# Sensor_Board.net
KiCad netlist of a schematic drawn in Altium Designer
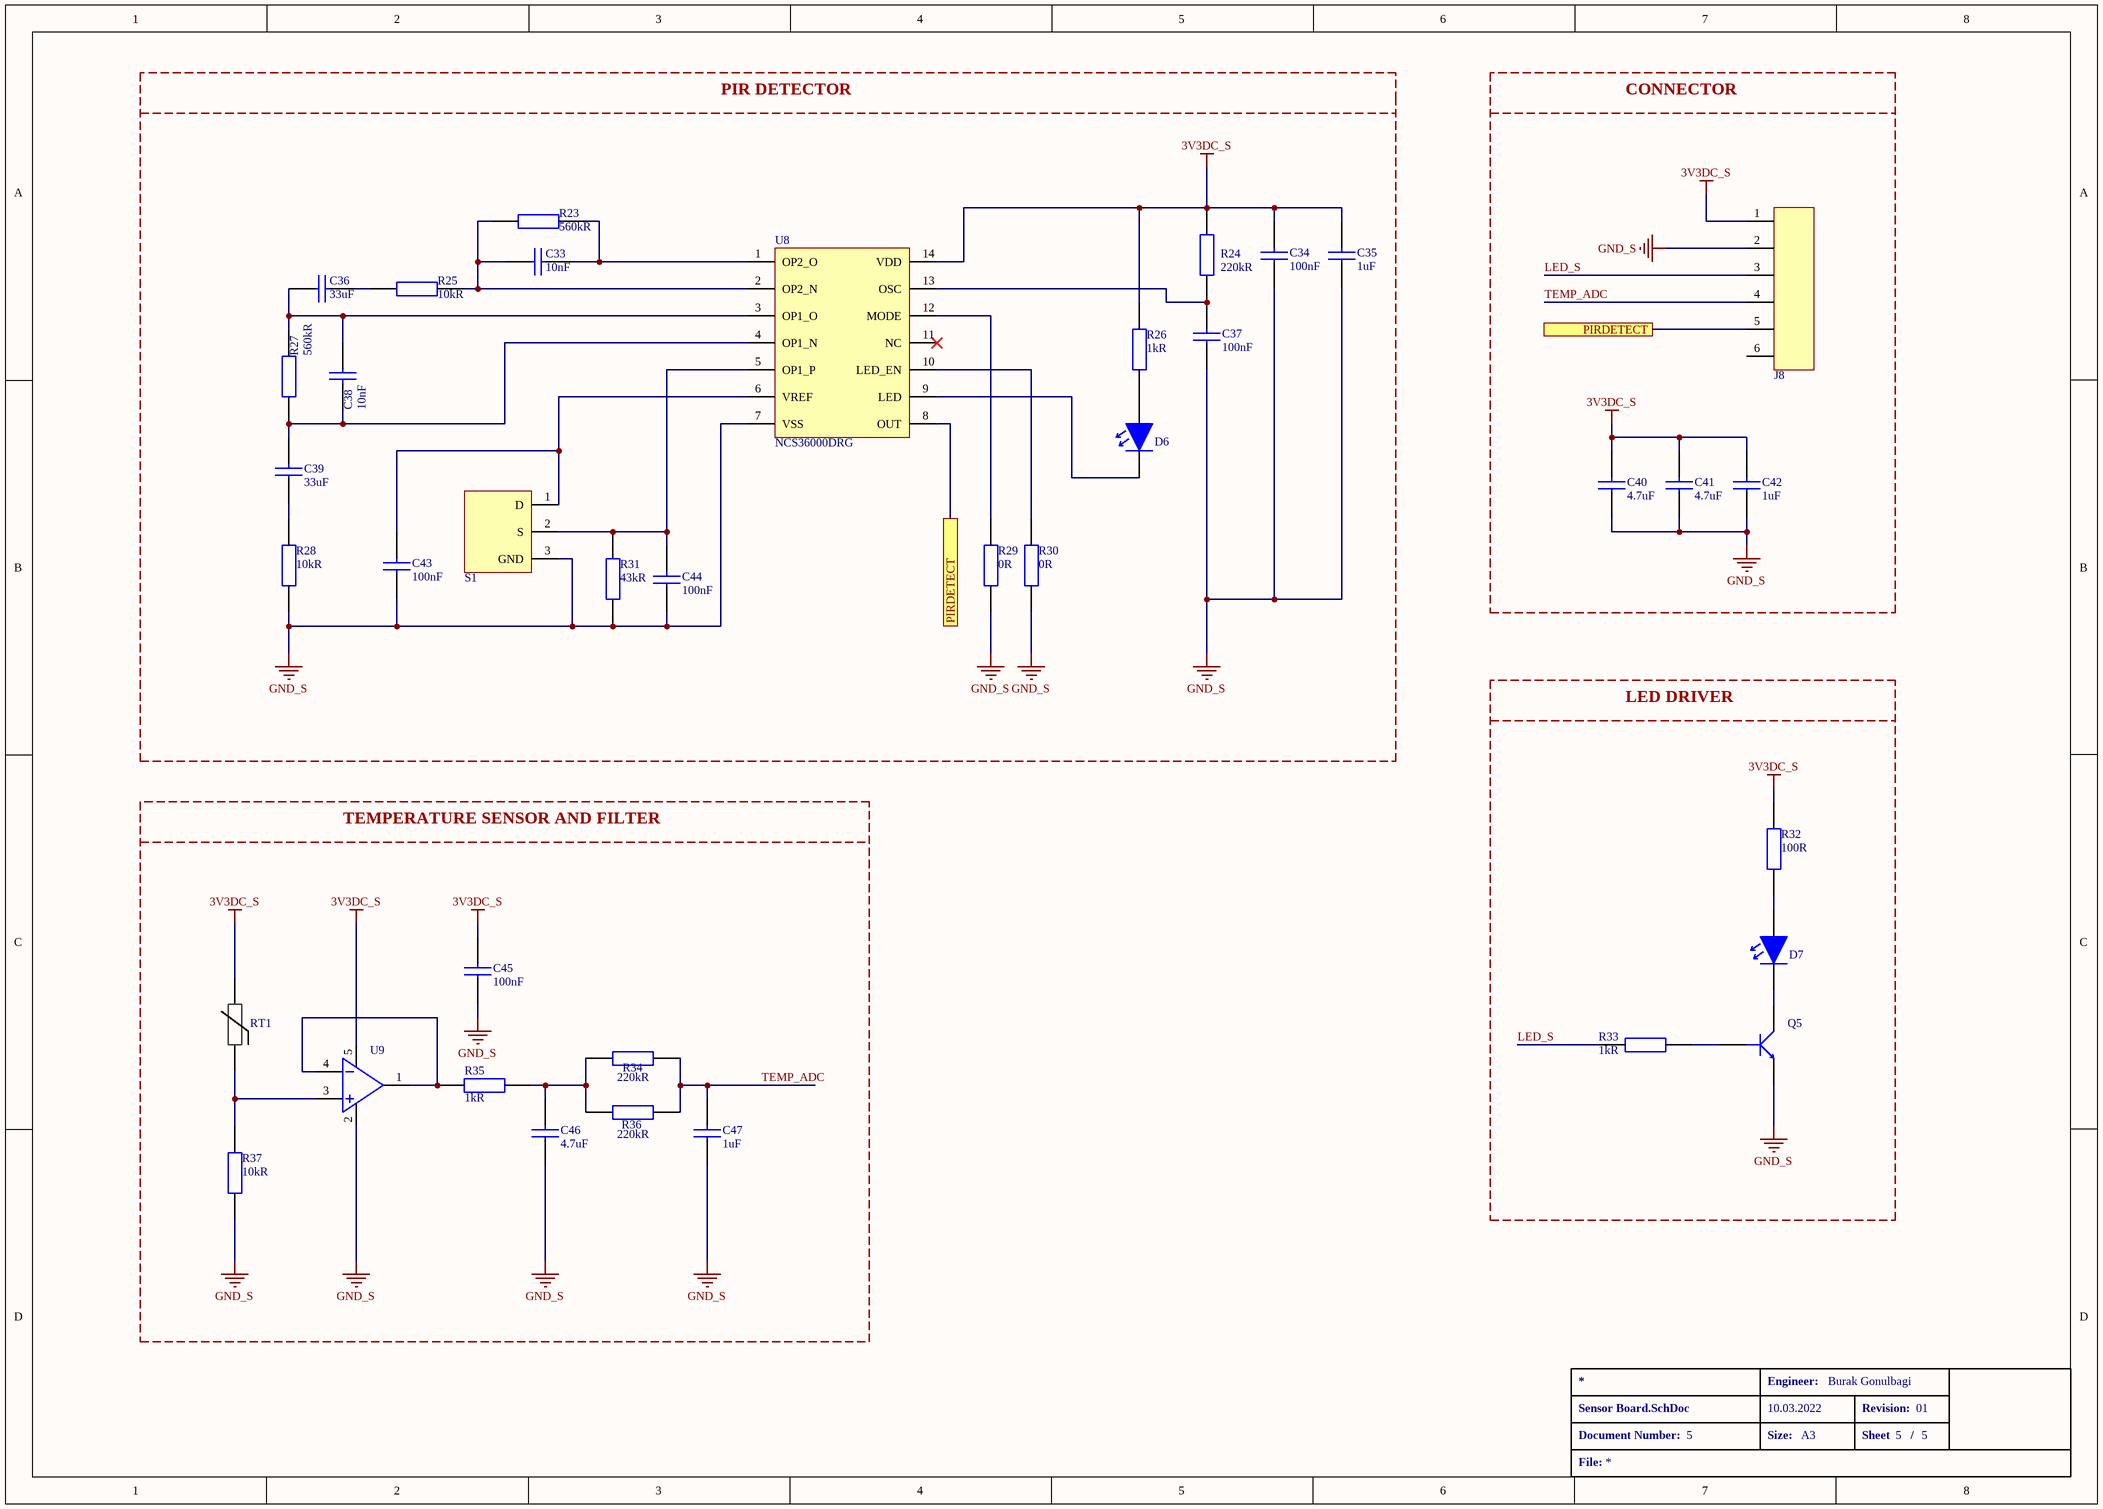
[diagram p0: Sensor Board.SchDoc]

(export (version "E")
  (design (tool "Eeschema 10.0.6"))
  (components
    (comp (ref "C33")
      (value "0603B103K160CT")
      (footprint "CAP_0603")
      (description "CAP CER 10nF %10 0603")
      (fields
        (field (name "MANUFACTURER") "Walsin Technologies")
        (field (name "TOLERANCE") "10%")
        (field (name "CAPACITANCE") "10nF")
        (field (name "DESIGNED BY") "BERK")
      )
      (libsource (lib "UDEMY_Library") (part "CAP CER 10nF 0603"))
    )
    (comp (ref "C34")
      (value "C0603C104K5RACTU")
      (footprint "CAP_0603")
      (description "CAP CER 100nF %10 0603 SMD")
      (fields
        (field (name "MANUFACTURER") "KEMET")
        (field (name "TOLERANCE") "10%")
        (field (name "CAPACITANCE") "100nF")
        (field (name "DESIGNED BY") "BERK")
      )
      (libsource (lib "UDEMY_Library") (part "CAP CER 100nF 0603"))
    )
    (comp (ref "C35")
      (value "CL21B105KBFNNNE")
      (footprint "CAP_0805")
      (description "CAP CER 1uF %10 0805")
      (fields
        (field (name "MANUFACTURER") "Samsung")
        (field (name "TOLERANCE") "10%")
        (field (name "CAPACITANCE") "1uF")
        (field (name "DESIGNED BY") "BERK")
      )
      (libsource (lib "UDEMY_Library") (part "CAP CER 1uF 0805"))
    )
    (comp (ref "C36")
      (value "C3216X5R1E336M160AC")
      (footprint "CAP_1206")
      (description "CAP CER 33uF %20 1206 SMD")
      (fields
        (field (name "MANUFACTURER") "TDK")
        (field (name "TOLERANCE") "20%")
        (field (name "CAPACITANCE") "33uF")
        (field (name "DESIGNED BY") "BERK")
      )
      (libsource (lib "UDEMY_Library") (part "CAP CER 33uF 1206"))
    )
    (comp (ref "C37")
      (value "C0603C104K5RACTU")
      (footprint "CAP_0603")
      (description "CAP CER 100nF %10 0603 SMD")
      (fields
        (field (name "MANUFACTURER") "KEMET")
        (field (name "TOLERANCE") "10%")
        (field (name "CAPACITANCE") "100nF")
        (field (name "DESIGNED BY") "BERK")
      )
      (libsource (lib "UDEMY_Library") (part "CAP CER 100nF 0603"))
    )
    (comp (ref "C38")
      (value "0603B103K160CT")
      (footprint "CAP_0603")
      (description "CAP CER 10nF %10 0603")
      (fields
        (field (name "MANUFACTURER") "Walsin Technologies")
        (field (name "TOLERANCE") "10%")
        (field (name "CAPACITANCE") "10nF")
        (field (name "DESIGNED BY") "BERK")
      )
      (libsource (lib "UDEMY_Library") (part "CAP CER 10nF 0603"))
    )
    (comp (ref "C39")
      (value "C3216X5R1E336M160AC")
      (footprint "CAP_1206")
      (description "CAP CER 33uF %20 1206 SMD")
      (fields
        (field (name "MANUFACTURER") "TDK")
        (field (name "TOLERANCE") "20%")
        (field (name "CAPACITANCE") "33uF")
        (field (name "DESIGNED BY") "BERK")
      )
      (libsource (lib "UDEMY_Library") (part "CAP CER 33uF 1206"))
    )
    (comp (ref "C40")
      (value "CL21A475KAQNNNE")
      (footprint "CAP_0805")
      (description "CAP CER 4.7uF %10 0805")
      (fields
        (field (name "MANUFACTURER") "Samsung")
        (field (name "TOLERANCE") "10%")
        (field (name "CAPACITANCE") "4.7uF")
        (field (name "DESIGNED BY") "BERK")
      )
      (libsource (lib "UDEMY_Library") (part "CAP CER 4.7uF 0805"))
    )
    (comp (ref "C41")
      (value "CL21A475KAQNNNE")
      (footprint "CAP_0805")
      (description "CAP CER 4.7uF %10 0805")
      (fields
        (field (name "MANUFACTURER") "Samsung")
        (field (name "TOLERANCE") "10%")
        (field (name "CAPACITANCE") "4.7uF")
        (field (name "DESIGNED BY") "BERK")
      )
      (libsource (lib "UDEMY_Library") (part "CAP CER 4.7uF 0805"))
    )
    (comp (ref "C42")
      (value "CL21B105KBFNNNE")
      (footprint "CAP_0805")
      (description "CAP CER 1uF %10 0805")
      (fields
        (field (name "MANUFACTURER") "Samsung")
        (field (name "TOLERANCE") "10%")
        (field (name "CAPACITANCE") "1uF")
        (field (name "DESIGNED BY") "BERK")
      )
      (libsource (lib "UDEMY_Library") (part "CAP CER 1uF 0805"))
    )
    (comp (ref "C43")
      (value "C0603C104K5RACTU")
      (footprint "CAP_0603")
      (description "CAP CER 100nF %10 0603 SMD")
      (fields
        (field (name "MANUFACTURER") "KEMET")
        (field (name "TOLERANCE") "10%")
        (field (name "CAPACITANCE") "100nF")
        (field (name "DESIGNED BY") "BERK")
      )
      (libsource (lib "UDEMY_Library") (part "CAP CER 100nF 0603"))
    )
    (comp (ref "C44")
      (value "C0603C104K5RACTU")
      (footprint "CAP_0603")
      (description "CAP CER 100nF %10 0603 SMD")
      (fields
        (field (name "MANUFACTURER") "KEMET")
        (field (name "TOLERANCE") "10%")
        (field (name "CAPACITANCE") "100nF")
        (field (name "DESIGNED BY") "BERK")
      )
      (libsource (lib "UDEMY_Library") (part "CAP CER 100nF 0603"))
    )
    (comp (ref "C45")
      (value "C0603C104K5RACTU")
      (footprint "CAP_0603")
      (description "CAP CER 100nF %10 0603 SMD")
      (fields
        (field (name "MANUFACTURER") "KEMET")
        (field (name "TOLERANCE") "10%")
        (field (name "CAPACITANCE") "100nF")
        (field (name "DESIGNED BY") "BERK")
      )
      (libsource (lib "UDEMY_Library") (part "CAP CER 100nF 0603"))
    )
    (comp (ref "C46")
      (value "CL21A475KAQNNNE")
      (footprint "CAP_0805")
      (description "CAP CER 4.7uF %10 0805")
      (fields
        (field (name "MANUFACTURER") "Samsung")
        (field (name "TOLERANCE") "10%")
        (field (name "CAPACITANCE") "4.7uF")
        (field (name "DESIGNED BY") "BERK")
      )
      (libsource (lib "UDEMY_Library") (part "CAP CER 4.7uF 0805"))
    )
    (comp (ref "C47")
      (value "CL21B105KBFNNNE")
      (footprint "CAP_0805")
      (description "CAP CER 1uF %10 0805")
      (fields
        (field (name "MANUFACTURER") "Samsung")
        (field (name "TOLERANCE") "10%")
        (field (name "CAPACITANCE") "1uF")
        (field (name "DESIGNED BY") "BERK")
      )
      (libsource (lib "UDEMY_Library") (part "CAP CER 1uF 0805"))
    )
    (comp (ref "D6")
      (value "LTST-C171GKT")
      (footprint "LED_GREEN_0805")
      (description "Green 0805 130 º Min 5 mcd Typical 12 mcd Water Clear Lens SMT LED")
      (fields (field (name "MANUFACTURER") "Vishay Lite-On") (field (name "DESIGNED BY") "BERK"))
      (libsource (lib "UDEMY_Library") (part "LED GREEN 0805"))
    )
    (comp (ref "D7")
      (value "LH R974-LP-1")
      (footprint "LED_RED_0805")
      (description "LED Uni-Color Hyper Red 660nm 2-Pin Chip 0805(2012Metric) T/R")
      (fields (field (name "MANUFACTURER") "Osram Opto") (field (name "DESIGNED BY") "BERK"))
      (libsource (lib "UDEMY_Library") (part "LED RED 0805"))
    )
    (comp (ref "J8")
      (value "64800611622")
      (footprint "64800611622")
      (description "1.50mm 6PIN Connector")
      (fields (field (name "MANUFACTURER") "Wurth Electronics"))
      (libsource (lib "UDEMY_Library") (part "64800611622_conn_6pin"))
    )
    (comp (ref "Q5")
      (value "MMBT3904-7-F")
      (footprint "SOT-23F")
      (description "Transistor General Purpose BJT NPN 40 Volt 0.2A Automotive 3-Pin SOT-23")
      (fields (field (name "MANUFACTURER") "Diodes Zetex") (field (name "DESIGNED BY") "BERK"))
      (libsource (lib "UDEMY_Library") (part "MMBT3904-7-F"))
    )
    (comp (ref "R23")
      (value "RC0603JR-07560KL")
      (footprint "RES_0603")
      (description "RES SMD 560K OHM 5% 1/10W 0603")
      (fields
        (field (name "MANUFACTURER") "Yageo")
        (field (name "TOLERANCE") "5%")
        (field (name "RESISTANCE") "560kR")
        (field (name "DESIGNED BY") "BERK")
      )
      (libsource (lib "") (part "RES 560K OHM 0603_1"))
    )
    (comp (ref "R24")
      (value "RC0603JR-07220KL")
      (footprint "RES_0603")
      (description "RES 220K %5 OHM 0603 SMD")
      (fields
        (field (name "MANUFACTURER") "Yageo")
        (field (name "TOLERANCE") "5%")
        (field (name "RESISTANCE") "220kR")
      )
      (libsource (lib "") (part "RES 220K OHM 0603_1"))
    )
    (comp (ref "R25")
      (value "RC0603FR-0710KL")
      (footprint "RES_0603")
      (description "RES 10K %1 OHM 0603 SMD")
      (fields
        (field (name "MANUFACTURER") "Yageo")
        (field (name "TOLERANCE") "1%")
        (field (name "RESISTANCE") "10kR")
        (field (name "DESIGNED BY") "BERK")
      )
      (libsource (lib "") (part "RES 10K OHM 0603_1"))
    )
    (comp (ref "R26")
      (value "RC0603FR-0710KL")
      (footprint "RES_0603")
      (description "RES 1K %1 OHM 0603 SMD")
      (fields
        (field (name "MANUFACTURER") "Yageo")
        (field (name "MANUFACTURER PART NUMBER") "RC0603JR-071KL")
        (field (name "RESISTANCE") "1kR")
        (field (name "DESIGNED BY") "BERK")
      )
      (libsource (lib "UDEMY_Library") (part "RES 1K OHM 0603"))
    )
    (comp (ref "R27")
      (value "RC0603JR-07560KL")
      (footprint "RES_0603")
      (description "RES SMD 560K OHM 5% 1/10W 0603")
      (fields
        (field (name "MANUFACTURER") "Yageo")
        (field (name "TOLERANCE") "5%")
        (field (name "RESISTANCE") "560kR")
        (field (name "DESIGNED BY") "BERK")
      )
      (libsource (lib "UDEMY_Library") (part "RES 560K OHM 0603"))
    )
    (comp (ref "R28")
      (value "RC0603FR-0710KL")
      (footprint "RES_0603")
      (description "RES 10K %1 OHM 0603 SMD")
      (fields
        (field (name "MANUFACTURER") "Yageo")
        (field (name "TOLERANCE") "1%")
        (field (name "RESISTANCE") "10kR")
        (field (name "DESIGNED BY") "BERK")
      )
      (libsource (lib "UDEMY_Library") (part "RES 10K OHM 0603"))
    )
    (comp (ref "R29")
      (value "RC0603JR-070RL")
      (footprint "RES_0603")
      (description "RES 0 %1 OHM 0603 SMD")
      (fields
        (field (name "MANUFACTURER") "Yageo")
        (field (name "TOLERANCE") "1%")
        (field (name "RESISTANCE") "0R")
        (field (name "DESIGNED BY") "BERK")
      )
      (libsource (lib "UDEMY_Library") (part "RES 0 OHM 0603"))
    )
    (comp (ref "R30")
      (value "RC0603JR-070RL")
      (footprint "RES_0603")
      (description "RES 0 %1 OHM 0603 SMD")
      (fields
        (field (name "MANUFACTURER") "Yageo")
        (field (name "TOLERANCE") "1%")
        (field (name "RESISTANCE") "0R")
        (field (name "DESIGNED BY") "BERK")
      )
      (libsource (lib "UDEMY_Library") (part "RES 0 OHM 0603"))
    )
    (comp (ref "R31")
      (value "RC0603JR-0743KL")
      (footprint "RES_0603")
      (description "RES 43K %5 OHM 0603 SMD")
      (fields
        (field (name "MANUFACTURER") "Yageo")
        (field (name "TOLERANCE") "5%")
        (field (name "RESISTANCE") "43kR")
        (field (name "DESIGNED BY") "BERK")
      )
      (libsource (lib "UDEMY_Library") (part "RES 43K OHM 0603"))
    )
    (comp (ref "R32")
      (value "RC0603JR-07100RL")
      (footprint "RES_0603")
      (description "RES 100 %5 OHM 0603 SMD")
      (fields
        (field (name "MANUFACTURER") "Yageo")
        (field (name "TOLERANCE") "5%")
        (field (name "RESISTANCE") "100R")
        (field (name "DESIGNED BY") "BERK")
      )
      (libsource (lib "UDEMY_Library") (part "RES 100 OHM 0603"))
    )
    (comp (ref "R33")
      (value "RC0603FR-0710KL")
      (footprint "RES_0603")
      (description "RES 1K %1 OHM 0603 SMD")
      (fields
        (field (name "MANUFACTURER") "Yageo")
        (field (name "MANUFACTURER PART NUMBER") "RC0603JR-071KL")
        (field (name "RESISTANCE") "1kR")
        (field (name "DESIGNED BY") "BERK")
      )
      (libsource (lib "") (part "RES 1K OHM 0603_1"))
    )
    (comp (ref "R34")
      (value "RC0603JR-07220KL")
      (footprint "RES_0603")
      (description "RES 220K %5 OHM 0603 SMD")
      (fields
        (field (name "MANUFACTURER") "Yageo")
        (field (name "TOLERANCE") "5%")
        (field (name "RESISTANCE") "220kR")
      )
      (libsource (lib "UDEMY_Library") (part "RES 220K OHM 0603"))
    )
    (comp (ref "R35")
      (value "RC0603FR-0710KL")
      (footprint "RES_0603")
      (description "RES 1K %1 OHM 0603 SMD")
      (fields
        (field (name "MANUFACTURER") "Yageo")
        (field (name "MANUFACTURER PART NUMBER") "RC0603JR-071KL")
        (field (name "RESISTANCE") "1kR")
        (field (name "DESIGNED BY") "BERK")
      )
      (libsource (lib "") (part "RES 1K OHM 0603_1"))
    )
    (comp (ref "R36")
      (value "RC0603JR-07220KL")
      (footprint "RES_0603")
      (description "RES 220K %5 OHM 0603 SMD")
      (fields
        (field (name "MANUFACTURER") "Yageo")
        (field (name "TOLERANCE") "5%")
        (field (name "RESISTANCE") "220kR")
      )
      (libsource (lib "UDEMY_Library") (part "RES 220K OHM 0603"))
    )
    (comp (ref "R37")
      (value "RC0603FR-0710KL")
      (footprint "RES_0603")
      (description "RES 10K %1 OHM 0603 SMD")
      (fields
        (field (name "MANUFACTURER") "Yageo")
        (field (name "TOLERANCE") "1%")
        (field (name "RESISTANCE") "10kR")
        (field (name "DESIGNED BY") "BERK")
      )
      (libsource (lib "UDEMY_Library") (part "RES 10K OHM 0603"))
    )
    (comp (ref "RT1")
      (value "TFPT1206L1002FM")
      (footprint "RES_1206")
      (description "Thermistor PTC 10K Ohm 1% 1206")
      (fields
        (field (name "MANUFACTURER") "Vishay Dale")
        (field (name "TOLERANCE") "1%")
        (field (name "DESIGNED BY") "BERK")
      )
      (libsource (lib "UDEMY_Library") (part "TFPT1206L1002FM"))
    )
    (comp (ref "S1")
      (value "LHI 878/3902")
      (footprint "LHI 878")
      (description "SENSOR PYRO DETECTOR DUAL MOTION")
      (fields (field (name "DESIGNED BY") "BERK"))
      (libsource (lib "UDEMY_Library") (part "LHI 878/3902"))
    )
    (comp (ref "U8")
      (value "NCS36000DRG")
      (footprint "SOIC14")
      (description "PIR Controller Low Noise Amplifiers and LDO Regulator 14-Pin SOIC N T/R")
      (fields (field (name "MANUFACTURER") "ON Semiconductor") (field (name "DESIGNED BY") "BERK"))
      (libsource (lib "UDEMY_Library") (part "NCS36000"))
    )
    (comp (ref "U9")
      (value "OPA314AIDBVR")
      (footprint "SOT23-5")
      (description "Op Amp OPA314")
      (fields (field (name "MANUFACTURER") "Texas Instruments") (field (name "DESIGNED BY") "BERK"))
      (libsource (lib "UDEMY_Library") (part "OPA314"))
    )
  )
  (nets
    (net (code "1") (name "/LED_S") (class "Default")
      (node (ref "J8") (pin "3") (pintype "power_in"))
      (node (ref "R33") (pin "1") (pinfunction "1_1") (pintype "passive"))
    )
    (net (code "2") (name "/PIRDETECT") (class "Default")
      (node (ref "J8") (pin "5") (pintype "power_in"))
      (node (ref "U8") (pin "8") (pinfunction "OUT_8") (pintype "passive"))
    )
    (net (code "3") (name "/TEMP_ADC") (class "Default")
      (node (ref "C47") (pin "2") (pinfunction "2_2") (pintype "passive"))
      (node (ref "J8") (pin "4") (pintype "power_in"))
      (node (ref "R34") (pin "2") (pinfunction "2_2") (pintype "passive"))
      (node (ref "R36") (pin "2") (pinfunction "2_2") (pintype "passive"))
    )
    (net (code "4") (name "3V3DC_S") (class "Default")
      (node (ref "C34") (pin "2") (pinfunction "2_2") (pintype "passive"))
      (node (ref "C35") (pin "2") (pinfunction "2_2") (pintype "passive"))
      (node (ref "C40") (pin "2") (pinfunction "2_2") (pintype "passive"))
      (node (ref "C41") (pin "2") (pinfunction "2_2") (pintype "passive"))
      (node (ref "C42") (pin "2") (pinfunction "2_2") (pintype "passive"))
      (node (ref "C45") (pin "2") (pinfunction "2_2") (pintype "passive"))
      (node (ref "J8") (pin "1") (pintype "power_in"))
      (node (ref "R24") (pin "2") (pinfunction "2_2") (pintype "passive"))
      (node (ref "R26") (pin "2") (pinfunction "2_2") (pintype "passive"))
      (node (ref "R32") (pin "2") (pinfunction "2_2") (pintype "passive"))
      (node (ref "RT1") (pin "2") (pinfunction "2_2") (pintype "passive"))
      (node (ref "U8") (pin "14") (pinfunction "VDD_14") (pintype "passive"))
      (node (ref "U9") (pin "5") (pinfunction "5_5") (pintype "passive"))
    )
    (net (code "5") (name "GND_S") (class "Default")
      (node (ref "C34") (pin "1") (pinfunction "1_1") (pintype "passive"))
      (node (ref "C35") (pin "1") (pinfunction "1_1") (pintype "passive"))
      (node (ref "C37") (pin "1") (pinfunction "1_1") (pintype "passive"))
      (node (ref "C40") (pin "1") (pinfunction "1_1") (pintype "passive"))
      (node (ref "C41") (pin "1") (pinfunction "1_1") (pintype "passive"))
      (node (ref "C42") (pin "1") (pinfunction "1_1") (pintype "passive"))
      (node (ref "C43") (pin "1") (pinfunction "1_1") (pintype "passive"))
      (node (ref "C44") (pin "1") (pinfunction "1_1") (pintype "passive"))
      (node (ref "C45") (pin "1") (pinfunction "1_1") (pintype "passive"))
      (node (ref "C46") (pin "1") (pinfunction "1_1") (pintype "passive"))
      (node (ref "C47") (pin "1") (pinfunction "1_1") (pintype "passive"))
      (node (ref "J8") (pin "2") (pintype "power_in"))
      (node (ref "Q5") (pin "2") (pinfunction "E_2") (pintype "power_in"))
      (node (ref "R28") (pin "1") (pinfunction "1_1") (pintype "passive"))
      (node (ref "R29") (pin "1") (pinfunction "1_1") (pintype "passive"))
      (node (ref "R30") (pin "1") (pinfunction "1_1") (pintype "passive"))
      (node (ref "R31") (pin "1") (pinfunction "1_1") (pintype "passive"))
      (node (ref "R37") (pin "1") (pinfunction "1_1") (pintype "passive"))
      (node (ref "S1") (pin "3") (pinfunction "GND_3") (pintype "passive"))
      (node (ref "U8") (pin "7") (pinfunction "VSS_7") (pintype "passive"))
      (node (ref "U9") (pin "2") (pinfunction "2_2") (pintype "passive"))
    )
    (net (code "6") (name "Net-(C36-Pad2)") (class "Default")
      (node (ref "C36") (pin "2") (pinfunction "2_2") (pintype "passive"))
      (node (ref "R25") (pin "1") (pinfunction "1_1") (pintype "passive"))
    )
    (net (code "7") (name "Net-(C39-Pad1)") (class "Default")
      (node (ref "C39") (pin "1") (pinfunction "1_1") (pintype "passive"))
      (node (ref "R28") (pin "2") (pinfunction "2_2") (pintype "passive"))
    )
    (net (code "8") (name "Net-(C46-Pad2)") (class "Default")
      (node (ref "C46") (pin "2") (pinfunction "2_2") (pintype "passive"))
      (node (ref "R34") (pin "1") (pinfunction "1_1") (pintype "passive"))
      (node (ref "R35") (pin "2") (pinfunction "2_2") (pintype "passive"))
      (node (ref "R36") (pin "1") (pinfunction "1_1") (pintype "passive"))
    )
    (net (code "9") (name "Net-(D6-Pad2)") (class "Default")
      (node (ref "D6") (pin "2") (pinfunction "2_2") (pintype "power_in"))
      (node (ref "R26") (pin "1") (pinfunction "1_1") (pintype "passive"))
    )
    (net (code "10") (name "Net-(D7-Pad2)") (class "Default")
      (node (ref "D7") (pin "2") (pinfunction "2_2") (pintype "power_in"))
      (node (ref "R32") (pin "1") (pinfunction "1_1") (pintype "passive"))
    )
    (net (code "11") (name "Net-(Q5-B)") (class "Default")
      (node (ref "Q5") (pin "1") (pinfunction "B_1") (pintype "power_in"))
      (node (ref "R33") (pin "2") (pinfunction "2_2") (pintype "passive"))
    )
    (net (code "12") (name "Net-(Q5-C)") (class "Default")
      (node (ref "D7") (pin "1") (pinfunction "1_1") (pintype "power_in"))
      (node (ref "Q5") (pin "3") (pinfunction "C_3") (pintype "power_in"))
    )
    (net (code "13") (name "Net-(R35-Pad1)") (class "Default")
      (node (ref "R35") (pin "1") (pinfunction "1_1") (pintype "passive"))
      (node (ref "U9") (pin "1") (pinfunction "1_1") (pintype "passive"))
      (node (ref "U9") (pin "4") (pinfunction "4_4") (pintype "passive"))
    )
    (net (code "14") (name "Net-(R37-Pad2)") (class "Default")
      (node (ref "R37") (pin "2") (pinfunction "2_2") (pintype "passive"))
      (node (ref "RT1") (pin "1") (pinfunction "1_1") (pintype "passive"))
      (node (ref "U9") (pin "3") (pinfunction "3_3") (pintype "passive"))
    )
    (net (code "15") (name "Net-(S1-D)") (class "Default")
      (node (ref "C43") (pin "2") (pinfunction "2_2") (pintype "passive"))
      (node (ref "S1") (pin "1") (pinfunction "D_1") (pintype "passive"))
      (node (ref "U8") (pin "6") (pinfunction "VREF_6") (pintype "passive"))
    )
    (net (code "16") (name "Net-(S1-S)") (class "Default")
      (node (ref "C44") (pin "2") (pinfunction "2_2") (pintype "passive"))
      (node (ref "R31") (pin "2") (pinfunction "2_2") (pintype "passive"))
      (node (ref "S1") (pin "2") (pinfunction "S_2") (pintype "passive"))
      (node (ref "U8") (pin "5") (pinfunction "OP1_P_5") (pintype "passive"))
    )
    (net (code "17") (name "Net-(U8-LED)") (class "Default")
      (node (ref "D6") (pin "1") (pinfunction "1_1") (pintype "power_in"))
      (node (ref "U8") (pin "9") (pinfunction "LED_9") (pintype "passive"))
    )
    (net (code "18") (name "Net-(U8-LED_EN)") (class "Default")
      (node (ref "R30") (pin "2") (pinfunction "2_2") (pintype "passive"))
      (node (ref "U8") (pin "10") (pinfunction "LED_EN_10") (pintype "passive"))
    )
    (net (code "19") (name "Net-(U8-MODE)") (class "Default")
      (node (ref "R29") (pin "2") (pinfunction "2_2") (pintype "passive"))
      (node (ref "U8") (pin "12") (pinfunction "MODE_12") (pintype "passive"))
    )
    (net (code "20") (name "Net-(U8-OP1_N)") (class "Default")
      (node (ref "C38") (pin "2") (pinfunction "2_2") (pintype "passive"))
      (node (ref "C39") (pin "2") (pinfunction "2_2") (pintype "passive"))
      (node (ref "R27") (pin "1") (pinfunction "1_1") (pintype "passive"))
      (node (ref "U8") (pin "4") (pinfunction "OP1_N_4") (pintype "passive"))
    )
    (net (code "21") (name "Net-(U8-OP1_O)") (class "Default")
      (node (ref "C36") (pin "1") (pinfunction "1_1") (pintype "passive"))
      (node (ref "C38") (pin "1") (pinfunction "1_1") (pintype "passive"))
      (node (ref "R27") (pin "2") (pinfunction "2_2") (pintype "passive"))
      (node (ref "U8") (pin "3") (pinfunction "OP1_O_3") (pintype "passive"))
    )
    (net (code "22") (name "Net-(U8-OP2_N)") (class "Default")
      (node (ref "C33") (pin "1") (pinfunction "1_1") (pintype "passive"))
      (node (ref "R23") (pin "1") (pinfunction "1_1") (pintype "passive"))
      (node (ref "R25") (pin "2") (pinfunction "2_2") (pintype "passive"))
      (node (ref "U8") (pin "2") (pinfunction "OP2_N_2") (pintype "passive"))
    )
    (net (code "23") (name "Net-(U8-OP2_O)") (class "Default")
      (node (ref "C33") (pin "2") (pinfunction "2_2") (pintype "passive"))
      (node (ref "R23") (pin "2") (pinfunction "2_2") (pintype "passive"))
      (node (ref "U8") (pin "1") (pinfunction "OP2_O_1") (pintype "passive"))
    )
    (net (code "24") (name "Net-(U8-OSC)") (class "Default")
      (node (ref "C37") (pin "2") (pinfunction "2_2") (pintype "passive"))
      (node (ref "R24") (pin "1") (pinfunction "1_1") (pintype "passive"))
      (node (ref "U8") (pin "13") (pinfunction "OSC_13") (pintype "passive"))
    )
    (net (code "25") (name "unconnected-(J8-Pad6)") (class "Default")
      (node (ref "J8") (pin "6") (pintype "power_in"))
    )
    (net (code "26") (name "unconnected-(U8-NC-Pad11)") (class "Default")
      (node (ref "U8") (pin "11") (pinfunction "NC_11") (pintype "passive+no_connect"))
    )
  )
)
